# M908B.net
KiCad netlist of a schematic drawn in EAGLE
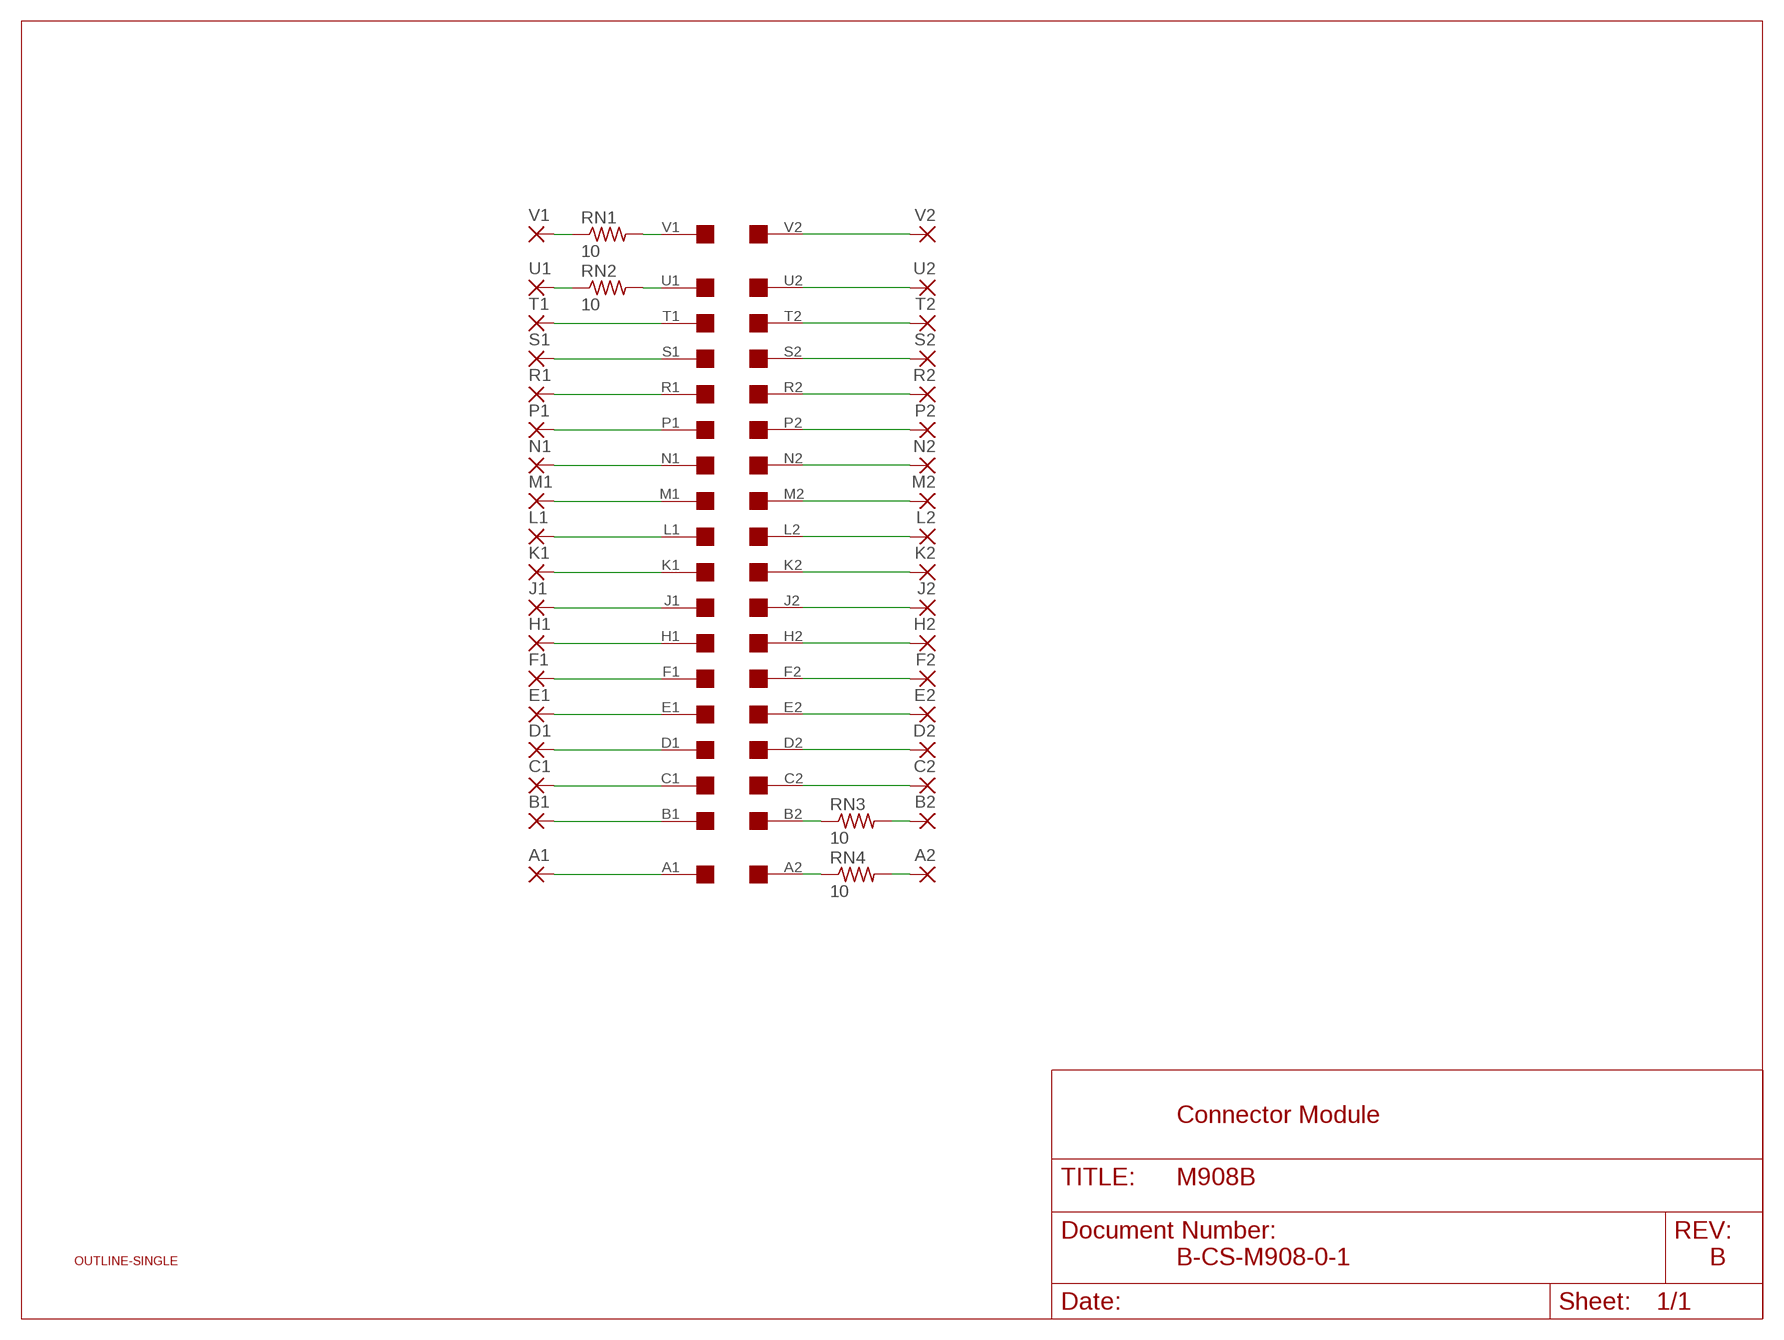
[diagram p0: schematic, sheet 1]

(export (version "E")
  (design (tool "Eeschema 10.0.6"))
  (components
    (comp (ref "A1")
      (value "2,54/1,0")
      (footprint "eagle-import:2,54_1,0")
      (libsource (lib "eagle-import") (part "2,54/1,0"))
    )
    (comp (ref "A2")
      (value "2,54/1,0")
      (footprint "eagle-import:2,54_1,0")
      (libsource (lib "eagle-import") (part "2,54/1,0"))
    )
    (comp (ref "B1")
      (value "2,54/1,0")
      (footprint "eagle-import:2,54_1,0")
      (libsource (lib "eagle-import") (part "2,54/1,0"))
    )
    (comp (ref "B2")
      (value "2,54/1,0")
      (footprint "eagle-import:2,54_1,0")
      (libsource (lib "eagle-import") (part "2,54/1,0"))
    )
    (comp (ref "C1")
      (value "2,54/1,0")
      (footprint "eagle-import:2,54_1,0")
      (libsource (lib "eagle-import") (part "2,54/1,0"))
    )
    (comp (ref "C2")
      (value "2,54/1,0")
      (footprint "eagle-import:2,54_1,0")
      (libsource (lib "eagle-import") (part "2,54/1,0"))
    )
    (comp (ref "D1")
      (value "2,54/1,0")
      (footprint "eagle-import:2,54_1,0")
      (libsource (lib "eagle-import") (part "2,54/1,0"))
    )
    (comp (ref "D2")
      (value "2,54/1,0")
      (footprint "eagle-import:2,54_1,0")
      (libsource (lib "eagle-import") (part "2,54/1,0"))
    )
    (comp (ref "E1")
      (value "2,54/1,0")
      (footprint "eagle-import:2,54_1,0")
      (libsource (lib "eagle-import") (part "2,54/1,0"))
    )
    (comp (ref "E2")
      (value "2,54/1,0")
      (footprint "eagle-import:2,54_1,0")
      (libsource (lib "eagle-import") (part "2,54/1,0"))
    )
    (comp (ref "F1")
      (value "2,54/1,0")
      (footprint "eagle-import:2,54_1,0")
      (libsource (lib "eagle-import") (part "2,54/1,0"))
    )
    (comp (ref "F2")
      (value "2,54/1,0")
      (footprint "eagle-import:2,54_1,0")
      (libsource (lib "eagle-import") (part "2,54/1,0"))
    )
    (comp (ref "H1")
      (value "2,54/1,0")
      (footprint "eagle-import:2,54_1,0")
      (libsource (lib "eagle-import") (part "2,54/1,0"))
    )
    (comp (ref "H2")
      (value "2,54/1,0")
      (footprint "eagle-import:2,54_1,0")
      (libsource (lib "eagle-import") (part "2,54/1,0"))
    )
    (comp (ref "J1")
      (value "2,54/1,0")
      (footprint "eagle-import:2,54_1,0")
      (libsource (lib "eagle-import") (part "2,54/1,0"))
    )
    (comp (ref "J2")
      (value "2,54/1,0")
      (footprint "eagle-import:2,54_1,0")
      (libsource (lib "eagle-import") (part "2,54/1,0"))
    )
    (comp (ref "K1")
      (value "2,54/1,0")
      (footprint "eagle-import:2,54_1,0")
      (libsource (lib "eagle-import") (part "2,54/1,0"))
    )
    (comp (ref "K2")
      (value "2,54/1,0")
      (footprint "eagle-import:2,54_1,0")
      (libsource (lib "eagle-import") (part "2,54/1,0"))
    )
    (comp (ref "L1")
      (value "2,54/1,0")
      (footprint "eagle-import:2,54_1,0")
      (libsource (lib "eagle-import") (part "2,54/1,0"))
    )
    (comp (ref "L2")
      (value "2,54/1,0")
      (footprint "eagle-import:2,54_1,0")
      (libsource (lib "eagle-import") (part "2,54/1,0"))
    )
    (comp (ref "M1")
      (value "2,54/1,0")
      (footprint "eagle-import:2,54_1,0")
      (libsource (lib "eagle-import") (part "2,54/1,0"))
    )
    (comp (ref "M2")
      (value "2,54/1,0")
      (footprint "eagle-import:2,54_1,0")
      (libsource (lib "eagle-import") (part "2,54/1,0"))
    )
    (comp (ref "N1")
      (value "2,54/1,0")
      (footprint "eagle-import:2,54_1,0")
      (libsource (lib "eagle-import") (part "2,54/1,0"))
    )
    (comp (ref "N2")
      (value "2,54/1,0")
      (footprint "eagle-import:2,54_1,0")
      (libsource (lib "eagle-import") (part "2,54/1,0"))
    )
    (comp (ref "P1")
      (value "2,54/1,0")
      (footprint "eagle-import:2,54_1,0")
      (libsource (lib "eagle-import") (part "2,54/1,0"))
    )
    (comp (ref "P2")
      (value "2,54/1,0")
      (footprint "eagle-import:2,54_1,0")
      (libsource (lib "eagle-import") (part "2,54/1,0"))
    )
    (comp (ref "R1")
      (value "2,54/1,0")
      (footprint "eagle-import:2,54_1,0")
      (libsource (lib "eagle-import") (part "2,54/1,0"))
    )
    (comp (ref "R2")
      (value "2,54/1,0")
      (footprint "eagle-import:2,54_1,0")
      (libsource (lib "eagle-import") (part "2,54/1,0"))
    )
    (comp (ref "RN1")
      (value "10")
      (footprint "eagle-import:0207_10")
      (libsource (lib "eagle-import") (part "R-US_0207/10"))
    )
    (comp (ref "RN2")
      (value "10")
      (footprint "eagle-import:0207_10")
      (libsource (lib "eagle-import") (part "R-US_0207/10"))
    )
    (comp (ref "RN3")
      (value "10")
      (footprint "eagle-import:0207_10")
      (libsource (lib "eagle-import") (part "R-US_0207/10"))
    )
    (comp (ref "RN4")
      (value "10")
      (footprint "eagle-import:0207_10")
      (libsource (lib "eagle-import") (part "R-US_0207/10"))
    )
    (comp (ref "S1")
      (value "2,54/1,0")
      (footprint "eagle-import:2,54_1,0")
      (libsource (lib "eagle-import") (part "2,54/1,0"))
    )
    (comp (ref "S2")
      (value "2,54/1,0")
      (footprint "eagle-import:2,54_1,0")
      (libsource (lib "eagle-import") (part "2,54/1,0"))
    )
    (comp (ref "T1")
      (value "2,54/1,0")
      (footprint "eagle-import:2,54_1,0")
      (libsource (lib "eagle-import") (part "2,54/1,0"))
    )
    (comp (ref "T2")
      (value "2,54/1,0")
      (footprint "eagle-import:2,54_1,0")
      (libsource (lib "eagle-import") (part "2,54/1,0"))
    )
    (comp (ref "U$1")
      (value "SINGLE")
      (footprint "eagle-import:EDGE-CON2")
      (libsource (lib "eagle-import") (part "SINGLE"))
    )
    (comp (ref "U$2")
      (value "OUTLINE-SINGLE")
      (footprint "eagle-import:SINGLE")
      (libsource (lib "eagle-import") (part "OUTLINE-SINGLE"))
    )
    (comp (ref "U1")
      (value "2,54/1,0")
      (footprint "eagle-import:2,54_1,0")
      (libsource (lib "eagle-import") (part "2,54/1,0"))
    )
    (comp (ref "U2")
      (value "2,54/1,0")
      (footprint "eagle-import:2,54_1,0")
      (libsource (lib "eagle-import") (part "2,54/1,0"))
    )
    (comp (ref "V1")
      (value "2,54/1,0")
      (footprint "eagle-import:2,54_1,0")
      (libsource (lib "eagle-import") (part "2,54/1,0"))
    )
    (comp (ref "V2")
      (value "2,54/1,0")
      (footprint "eagle-import:2,54_1,0")
      (libsource (lib "eagle-import") (part "2,54/1,0"))
    )
  )
  (nets
    (net (code "1") (name "Net-(A1-P)") (class "Default")
      (node (ref "A1") (pin "1") (pinfunction "P_1") (pintype "passive"))
      (node (ref "U$1") (pin "A1") (pinfunction "1_A1") (pintype "bidirectional"))
    )
    (net (code "2") (name "Net-(A2-P)") (class "Default")
      (node (ref "A2") (pin "1") (pinfunction "P_1") (pintype "passive"))
      (node (ref "RN4") (pin "2") (pinfunction "2_2") (pintype "passive"))
    )
    (net (code "3") (name "Net-(B1-P)") (class "Default")
      (node (ref "B1") (pin "1") (pinfunction "P_1") (pintype "passive"))
      (node (ref "U$1") (pin "B1") (pinfunction "1_B1") (pintype "bidirectional"))
    )
    (net (code "4") (name "Net-(B2-P)") (class "Default")
      (node (ref "B2") (pin "1") (pinfunction "P_1") (pintype "passive"))
      (node (ref "RN3") (pin "2") (pinfunction "2_2") (pintype "passive"))
    )
    (net (code "5") (name "Net-(C1-P)") (class "Default")
      (node (ref "C1") (pin "1") (pinfunction "P_1") (pintype "passive"))
      (node (ref "U$1") (pin "C1") (pinfunction "1_C1") (pintype "bidirectional"))
    )
    (net (code "6") (name "Net-(C2-P)") (class "Default")
      (node (ref "C2") (pin "1") (pinfunction "P_1") (pintype "passive"))
      (node (ref "U$1") (pin "C2") (pinfunction "1_C2") (pintype "bidirectional"))
    )
    (net (code "7") (name "Net-(D1-P)") (class "Default")
      (node (ref "D1") (pin "1") (pinfunction "P_1") (pintype "passive"))
      (node (ref "U$1") (pin "D1") (pinfunction "1_D1") (pintype "bidirectional"))
    )
    (net (code "8") (name "Net-(D2-P)") (class "Default")
      (node (ref "D2") (pin "1") (pinfunction "P_1") (pintype "passive"))
      (node (ref "U$1") (pin "D2") (pinfunction "1_D2") (pintype "bidirectional"))
    )
    (net (code "9") (name "Net-(E1-P)") (class "Default")
      (node (ref "E1") (pin "1") (pinfunction "P_1") (pintype "passive"))
      (node (ref "U$1") (pin "E1") (pinfunction "1_E1") (pintype "bidirectional"))
    )
    (net (code "10") (name "Net-(E2-P)") (class "Default")
      (node (ref "E2") (pin "1") (pinfunction "P_1") (pintype "passive"))
      (node (ref "U$1") (pin "E2") (pinfunction "1_E2") (pintype "bidirectional"))
    )
    (net (code "11") (name "Net-(F1-P)") (class "Default")
      (node (ref "F1") (pin "1") (pinfunction "P_1") (pintype "passive"))
      (node (ref "U$1") (pin "F1") (pinfunction "1_F1") (pintype "bidirectional"))
    )
    (net (code "12") (name "Net-(F2-P)") (class "Default")
      (node (ref "F2") (pin "1") (pinfunction "P_1") (pintype "passive"))
      (node (ref "U$1") (pin "F2") (pinfunction "1_F2") (pintype "bidirectional"))
    )
    (net (code "13") (name "Net-(H1-P)") (class "Default")
      (node (ref "H1") (pin "1") (pinfunction "P_1") (pintype "passive"))
      (node (ref "U$1") (pin "H1") (pinfunction "1_H1") (pintype "bidirectional"))
    )
    (net (code "14") (name "Net-(H2-P)") (class "Default")
      (node (ref "H2") (pin "1") (pinfunction "P_1") (pintype "passive"))
      (node (ref "U$1") (pin "H2") (pinfunction "1_H2") (pintype "bidirectional"))
    )
    (net (code "15") (name "Net-(J1-P)") (class "Default")
      (node (ref "J1") (pin "1") (pinfunction "P_1") (pintype "passive"))
      (node (ref "U$1") (pin "J1") (pinfunction "1_J1") (pintype "bidirectional"))
    )
    (net (code "16") (name "Net-(J2-P)") (class "Default")
      (node (ref "J2") (pin "1") (pinfunction "P_1") (pintype "passive"))
      (node (ref "U$1") (pin "J2") (pinfunction "1_J2") (pintype "bidirectional"))
    )
    (net (code "17") (name "Net-(K1-P)") (class "Default")
      (node (ref "K1") (pin "1") (pinfunction "P_1") (pintype "passive"))
      (node (ref "U$1") (pin "K1") (pinfunction "1_K1") (pintype "bidirectional"))
    )
    (net (code "18") (name "Net-(K2-P)") (class "Default")
      (node (ref "K2") (pin "1") (pinfunction "P_1") (pintype "passive"))
      (node (ref "U$1") (pin "K2") (pinfunction "1_K2") (pintype "bidirectional"))
    )
    (net (code "19") (name "Net-(L1-P)") (class "Default")
      (node (ref "L1") (pin "1") (pinfunction "P_1") (pintype "passive"))
      (node (ref "U$1") (pin "L1") (pinfunction "1_L1") (pintype "bidirectional"))
    )
    (net (code "20") (name "Net-(L2-P)") (class "Default")
      (node (ref "L2") (pin "1") (pinfunction "P_1") (pintype "passive"))
      (node (ref "U$1") (pin "L2") (pinfunction "1_L2") (pintype "bidirectional"))
    )
    (net (code "21") (name "Net-(M1-P)") (class "Default")
      (node (ref "M1") (pin "1") (pinfunction "P_1") (pintype "passive"))
      (node (ref "U$1") (pin "M1") (pinfunction "1_M1") (pintype "bidirectional"))
    )
    (net (code "22") (name "Net-(M2-P)") (class "Default")
      (node (ref "M2") (pin "1") (pinfunction "P_1") (pintype "passive"))
      (node (ref "U$1") (pin "M2") (pinfunction "1_M2") (pintype "bidirectional"))
    )
    (net (code "23") (name "Net-(N1-P)") (class "Default")
      (node (ref "N1") (pin "1") (pinfunction "P_1") (pintype "passive"))
      (node (ref "U$1") (pin "N1") (pinfunction "1_N1") (pintype "bidirectional"))
    )
    (net (code "24") (name "Net-(N2-P)") (class "Default")
      (node (ref "N2") (pin "1") (pinfunction "P_1") (pintype "passive"))
      (node (ref "U$1") (pin "N2") (pinfunction "1_N2") (pintype "bidirectional"))
    )
    (net (code "25") (name "Net-(P1-P)") (class "Default")
      (node (ref "P1") (pin "1") (pinfunction "P_1") (pintype "passive"))
      (node (ref "U$1") (pin "P1") (pinfunction "1_P1") (pintype "bidirectional"))
    )
    (net (code "26") (name "Net-(P2-P)") (class "Default")
      (node (ref "P2") (pin "1") (pinfunction "P_1") (pintype "passive"))
      (node (ref "U$1") (pin "P2") (pinfunction "1_P2") (pintype "bidirectional"))
    )
    (net (code "27") (name "Net-(R1-P)") (class "Default")
      (node (ref "R1") (pin "1") (pinfunction "P_1") (pintype "passive"))
      (node (ref "U$1") (pin "R1") (pinfunction "1_R1") (pintype "bidirectional"))
    )
    (net (code "28") (name "Net-(R2-P)") (class "Default")
      (node (ref "R2") (pin "1") (pinfunction "P_1") (pintype "passive"))
      (node (ref "U$1") (pin "R2") (pinfunction "1_R2") (pintype "bidirectional"))
    )
    (net (code "29") (name "Net-(S1-P)") (class "Default")
      (node (ref "S1") (pin "1") (pinfunction "P_1") (pintype "passive"))
      (node (ref "U$1") (pin "S1") (pinfunction "1_S1") (pintype "bidirectional"))
    )
    (net (code "30") (name "Net-(S2-P)") (class "Default")
      (node (ref "S2") (pin "1") (pinfunction "P_1") (pintype "passive"))
      (node (ref "U$1") (pin "S2") (pinfunction "1_S2") (pintype "bidirectional"))
    )
    (net (code "31") (name "Net-(T1-P)") (class "Default")
      (node (ref "T1") (pin "1") (pinfunction "P_1") (pintype "passive"))
      (node (ref "U$1") (pin "T1") (pinfunction "1_T1") (pintype "bidirectional"))
    )
    (net (code "32") (name "Net-(T2-P)") (class "Default")
      (node (ref "T2") (pin "1") (pinfunction "P_1") (pintype "passive"))
      (node (ref "U$1") (pin "T2") (pinfunction "1_T2") (pintype "bidirectional"))
    )
    (net (code "33") (name "Net-(U$1AG-1)") (class "Default")
      (node (ref "RN2") (pin "2") (pinfunction "2_2") (pintype "passive"))
      (node (ref "U$1") (pin "U1") (pinfunction "1_U1") (pintype "bidirectional"))
    )
    (net (code "34") (name "Net-(U$1AH-1)") (class "Default")
      (node (ref "U$1") (pin "U2") (pinfunction "1_U2") (pintype "bidirectional"))
      (node (ref "U2") (pin "1") (pinfunction "P_1") (pintype "passive"))
    )
    (net (code "35") (name "Net-(U$1AI-1)") (class "Default")
      (node (ref "RN1") (pin "2") (pinfunction "2_2") (pintype "passive"))
      (node (ref "U$1") (pin "V1") (pinfunction "1_V1") (pintype "bidirectional"))
    )
    (net (code "36") (name "Net-(U$1AJ-1)") (class "Default")
      (node (ref "U$1") (pin "V2") (pinfunction "1_V2") (pintype "bidirectional"))
      (node (ref "V2") (pin "1") (pinfunction "P_1") (pintype "passive"))
    )
    (net (code "37") (name "Net-(U$1B-1)") (class "Default")
      (node (ref "RN4") (pin "1") (pinfunction "1_1") (pintype "passive"))
      (node (ref "U$1") (pin "A2") (pinfunction "1_A2") (pintype "bidirectional"))
    )
    (net (code "38") (name "Net-(U$1D-1)") (class "Default")
      (node (ref "RN3") (pin "1") (pinfunction "1_1") (pintype "passive"))
      (node (ref "U$1") (pin "B2") (pinfunction "1_B2") (pintype "bidirectional"))
    )
    (net (code "39") (name "Net-(U1-P)") (class "Default")
      (node (ref "RN2") (pin "1") (pinfunction "1_1") (pintype "passive"))
      (node (ref "U1") (pin "1") (pinfunction "P_1") (pintype "passive"))
    )
    (net (code "40") (name "Net-(V1-P)") (class "Default")
      (node (ref "RN1") (pin "1") (pinfunction "1_1") (pintype "passive"))
      (node (ref "V1") (pin "1") (pinfunction "P_1") (pintype "passive"))
    )
  )
)
